# HW1_17.net
KiCad netlist of a schematic drawn in EasyEDA
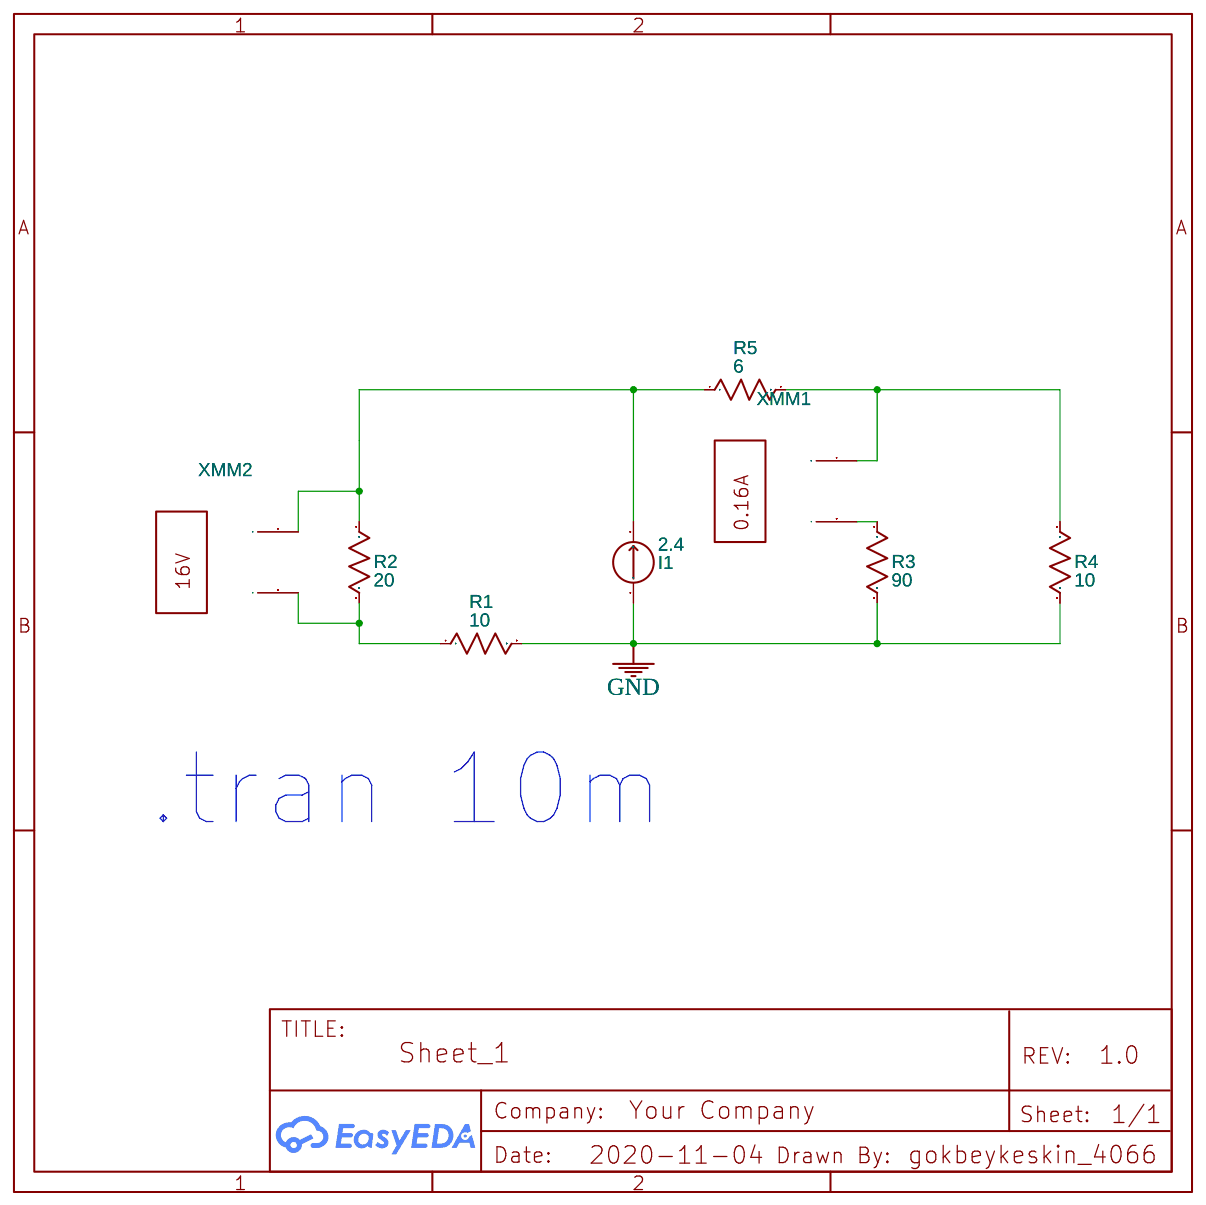
[diagram p0: schematic sheet]

(export (version "E")
  (design (tool "Eeschema 10.0.6"))
  (components
    (comp (ref "I1") (value "2.4") (libsource (lib "") (part "IDC")))
    (comp (ref "R1") (value "10") (libsource (lib "") (part "Resistor_US")))
    (comp (ref "R2") (value "20") (libsource (lib "") (part "Resistor_US_1")))
    (comp (ref "R3") (value "90") (libsource (lib "") (part "Resistor_US_1")))
    (comp (ref "R4") (value "10") (libsource (lib "") (part "Resistor_US_1")))
    (comp (ref "R5") (value "6") (libsource (lib "") (part "Resistor_US")))
    (comp (ref "XMM1") (value "Multimeter") (libsource (lib "") (part "MULTIMETER_1")))
    (comp (ref "XMM2") (value "Multimeter") (libsource (lib "") (part "MULTIMETER")))
  )
  (nets
    (net (code "1") (name "GND") (class "Default")
      (node (ref "I1") (pin "1") (pinfunction "1_1") (pintype "unspecified"))
      (node (ref "R1") (pin "2") (pinfunction "2_2") (pintype "unspecified"))
      (node (ref "R3") (pin "2") (pinfunction "2_2") (pintype "unspecified"))
      (node (ref "R4") (pin "2") (pinfunction "2_2") (pintype "unspecified"))
    )
    (net (code "2") (name "Net-(XMM1-+)") (class "Default")
      (node (ref "R4") (pin "1") (pinfunction "1_1") (pintype "unspecified"))
      (node (ref "R5") (pin "2") (pinfunction "2_2") (pintype "unspecified"))
      (node (ref "XMM1") (pin "1") (pinfunction "+_1") (pintype "unspecified"))
    )
    (net (code "3") (name "Net-(XMM1-I)") (class "Default")
      (node (ref "R3") (pin "1") (pinfunction "1_1") (pintype "unspecified"))
      (node (ref "XMM1") (pin "2") (pinfunction "I_2") (pintype "unspecified"))
    )
    (net (code "4") (name "Net-(XMM2-+)") (class "Default")
      (node (ref "I1") (pin "2") (pinfunction "2_2") (pintype "unspecified"))
      (node (ref "R2") (pin "1") (pinfunction "1_1") (pintype "unspecified"))
      (node (ref "R5") (pin "1") (pinfunction "1_1") (pintype "unspecified"))
      (node (ref "XMM2") (pin "1") (pinfunction "+_1") (pintype "unspecified"))
    )
    (net (code "5") (name "Net-(XMM2-I)") (class "Default")
      (node (ref "R1") (pin "1") (pinfunction "1_1") (pintype "unspecified"))
      (node (ref "R2") (pin "2") (pinfunction "2_2") (pintype "unspecified"))
      (node (ref "XMM2") (pin "2") (pinfunction "I_2") (pintype "unspecified"))
    )
  )
)
